# bender_isometer_interface.net
KiCad netlist of a schematic drawn in Altium Designer
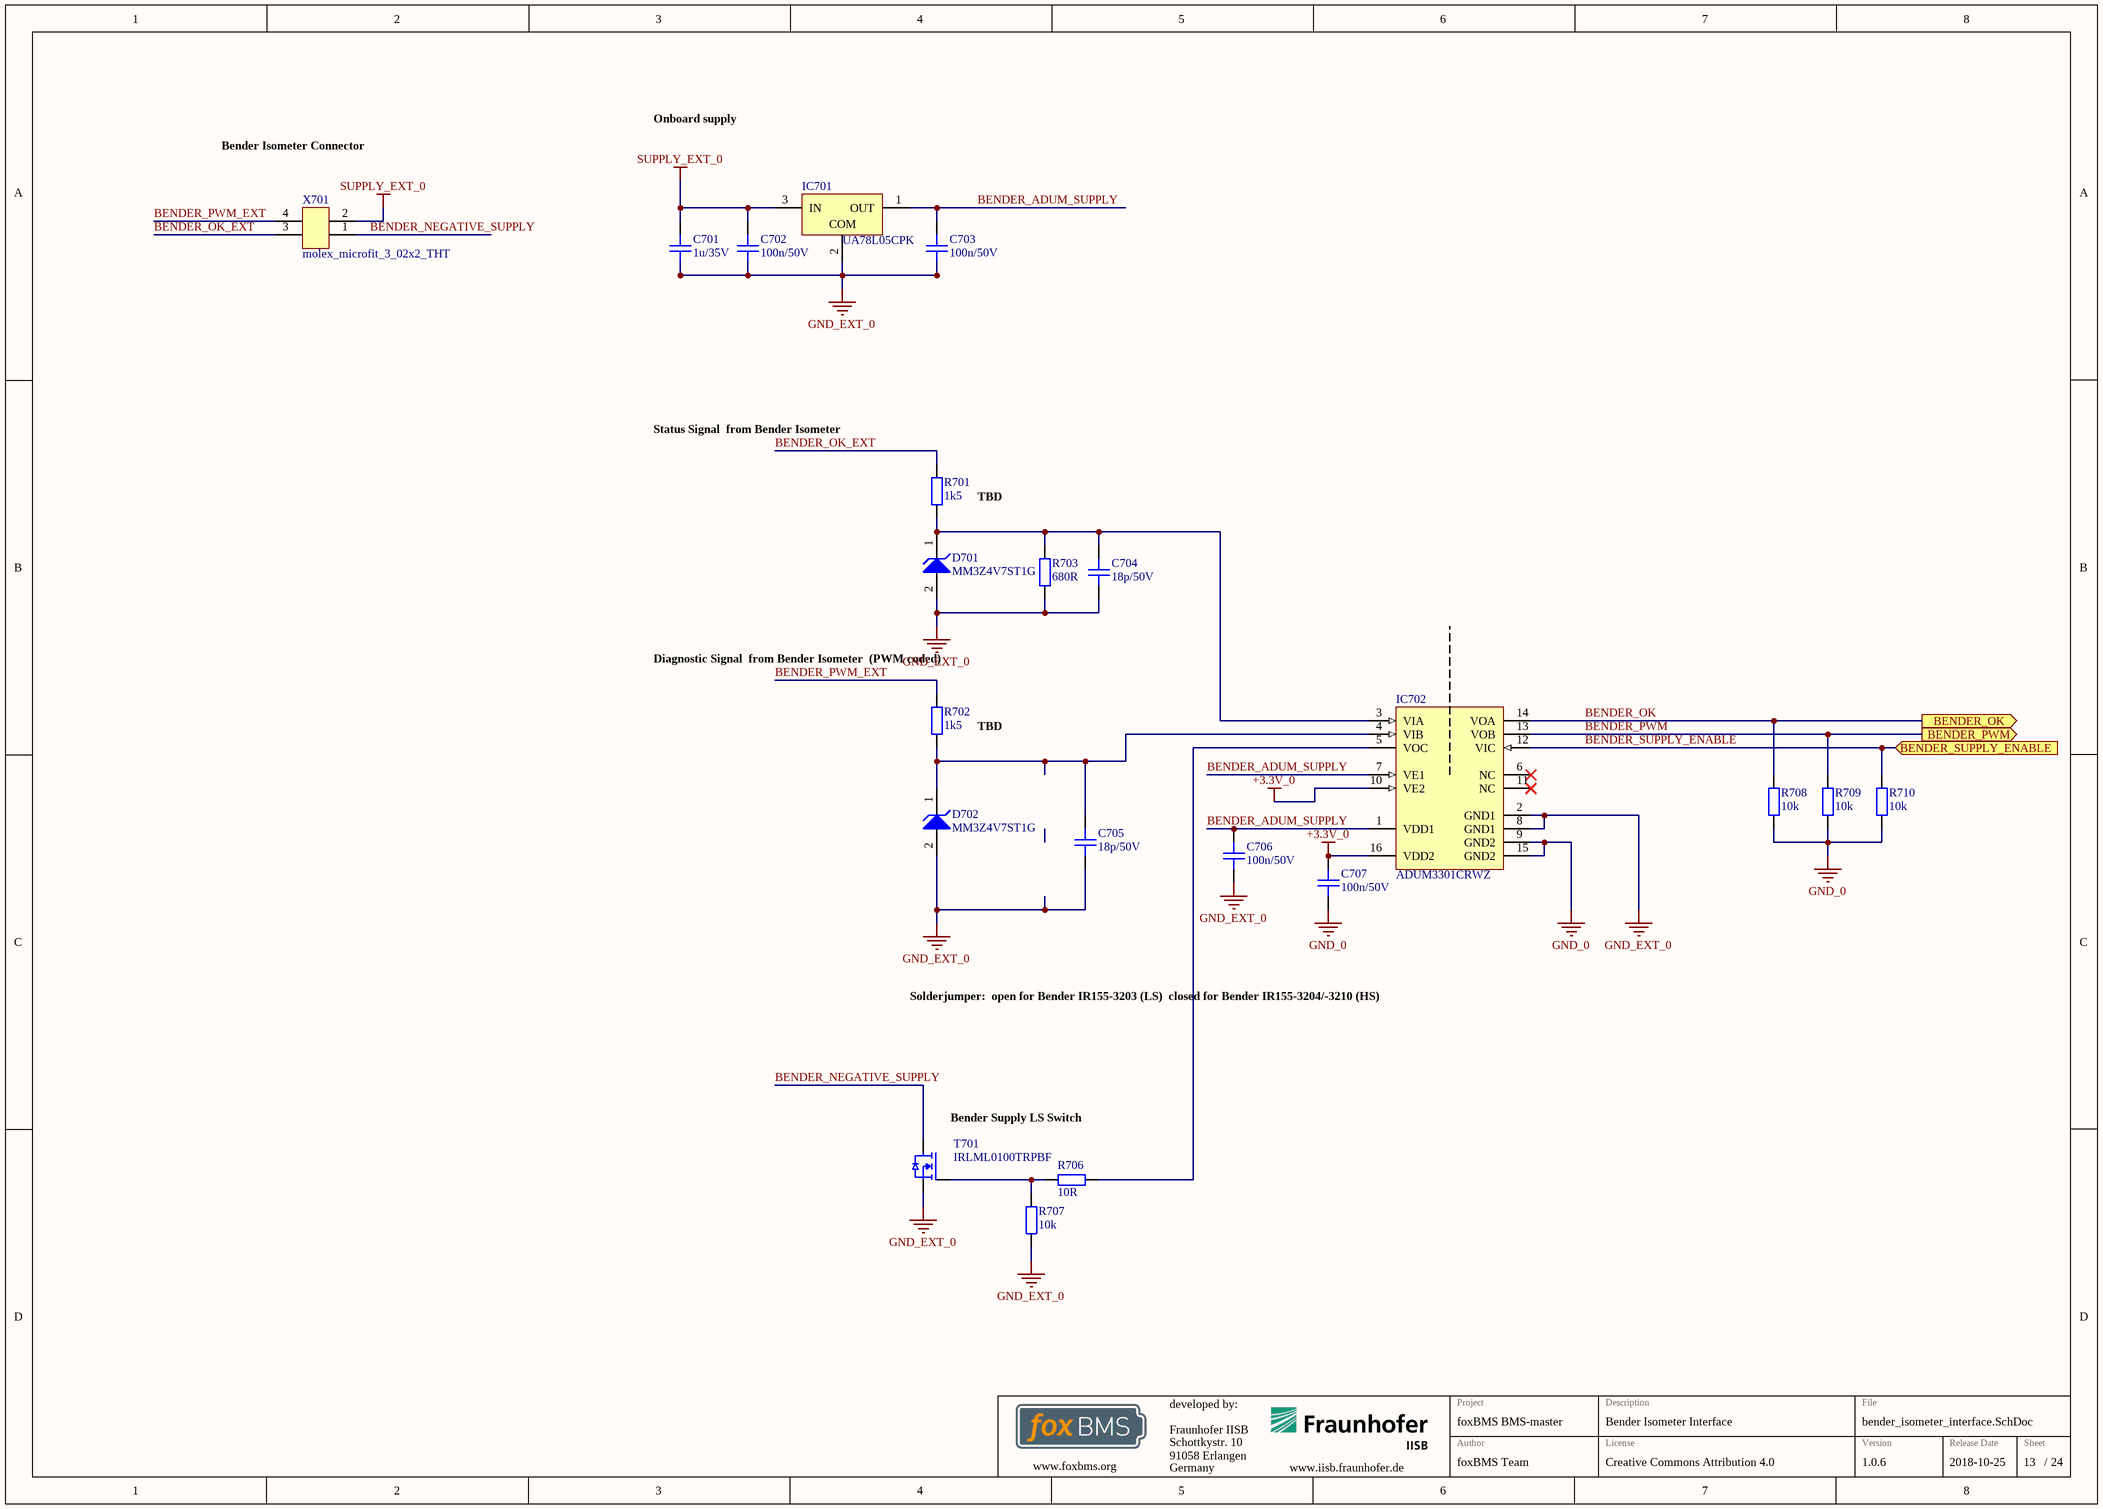
[diagram p0: bender_isometer_interface.SchDoc]

(export (version "E")
  (design (tool "Eeschema 10.0.6"))
  (components
    (comp (ref "C701")
      (value "1u/35V")
      (footprint "CAPC1608X08N")
      (description "MLCC")
      (fields (field (name "PART NUMBER") "gen_C_ceramic_1u_35V_X7R_0603"))
      (libsource (lib "OE750") (part "C"))
    )
    (comp (ref "C702")
      (value "100n/50V")
      (footprint "CAPC1608X08N")
      (description "MLCC")
      (fields (field (name "PART NUMBER") "gen_C_ceramic_100n_50V_X7R_0603"))
      (libsource (lib "OE750") (part "C"))
    )
    (comp (ref "C703")
      (value "100n/50V")
      (footprint "CAPC1608X08N")
      (description "MLCC")
      (fields (field (name "PART NUMBER") "gen_C_ceramic_100n_50V_X7R_0603"))
      (libsource (lib "OE750") (part "C"))
    )
    (comp (ref "C704")
      (value "18p/50V")
      (footprint "CAPC1608X08N")
      (description "MLCC")
      (fields (field (name "PART NUMBER") "gen_C_ceramic_18p_50V_C0G_0603"))
      (libsource (lib "OE750") (part "C"))
    )
    (comp (ref "C705")
      (value "18p/50V")
      (footprint "CAPC1608X08N")
      (description "MLCC")
      (fields (field (name "PART NUMBER") "gen_C_ceramic_18p_50V_C0G_0603"))
      (libsource (lib "OE750") (part "C"))
    )
    (comp (ref "C706")
      (value "100n/50V")
      (footprint "CAPC1608X08N")
      (description "MLCC")
      (fields (field (name "PART NUMBER") "gen_C_ceramic_100n_50V_X7R_0603"))
      (libsource (lib "OE750") (part "C"))
    )
    (comp (ref "C707")
      (value "100n/50V")
      (footprint "CAPC1608X08N")
      (description "MLCC")
      (fields (field (name "PART NUMBER") "gen_C_ceramic_100n_50V_X7R_0603"))
      (libsource (lib "OE750") (part "C"))
    )
    (comp (ref "D701")
      (value "MM3Z4V7ST1G")
      (footprint "ONSC-SOD-323-2-477-02_V")
      (description "Zener Voltage Regulator, 300 mW, Tight Tolerance Portfolio, 2-Pin SOD-323, Pb-Free, Tape and Reel")
      (fields (field (name "MANUFACTURER") "On Semiconductor"))
      (libsource (lib "Altium Content Vault") (part "ONSC-K1A2-2"))
    )
    (comp (ref "D702")
      (value "MM3Z4V7ST1G")
      (footprint "ONSC-SOD-323-2-477-02_V")
      (description "Zener Voltage Regulator, 300 mW, Tight Tolerance Portfolio, 2-Pin SOD-323, Pb-Free, Tape and Reel")
      (fields (field (name "MANUFACTURER") "On Semiconductor"))
      (libsource (lib "Altium Content Vault") (part "ONSC-K1A2-2"))
    )
    (comp (ref "IC701")
      (value "UA78L05CPK")
      (footprint "PK0003A_L")
      (fields (field (name "MANUFACTURER") "TexasInstruments"))
      (libsource (lib "Altium Content Vault") (part "TI-UA78L05-PK-3"))
    )
    (comp (ref "IC702")
      (value "ADUM3301CRWZ")
      (footprint "ADI-RW-16_N")
      (fields (field (name "MANUFACTURER") "Analog Devices"))
      (libsource (lib "Altium Content Vault") (part "ADI-ADUMX301-RW-16"))
    )
    (comp (ref "R701")
      (value "1k5")
      (footprint "RESC1608X05N")
      (description "SMD Resistor 1k5 0603")
      (fields (field (name "PART NUMBER") "gen_R_1k5_0603") (field (name "TOLERANCE") "1%"))
      (libsource (lib "OE750") (part "R"))
    )
    (comp (ref "R702")
      (value "1k5")
      (footprint "RESC1608X05N")
      (description "SMD Resistor 1k5 0603")
      (fields (field (name "PART NUMBER") "gen_R_1k5_0603") (field (name "TOLERANCE") "1%"))
      (libsource (lib "OE750") (part "R"))
    )
    (comp (ref "R703")
      (value "680R")
      (footprint "RESC1608X05N")
      (description "SMD Resistor 680R 0603")
      (fields (field (name "PART NUMBER") "gen_R_680R_0603") (field (name "TOLERANCE") "1%"))
      (libsource (lib "OE750") (part "R"))
    )
    (comp (ref "R706")
      (value "10R")
      (footprint "RESC1608X05N")
      (description "SMD Resistor 10R 0603")
      (fields (field (name "PART NUMBER") "gen_R_10R_0603") (field (name "TOLERANCE") "1%"))
      (libsource (lib "OE750") (part "R"))
    )
    (comp (ref "R707")
      (value "10k")
      (footprint "RESC1608X05N")
      (description "SMD Resistor 10k 0603")
      (fields (field (name "PART NUMBER") "gen_R_10k_0603") (field (name "TOLERANCE") "1%"))
      (libsource (lib "OE750") (part "R"))
    )
    (comp (ref "R708")
      (value "10k")
      (footprint "RESC1608X05N")
      (description "SMD Resistor 10k 0603")
      (fields (field (name "PART NUMBER") "gen_R_10k_0603") (field (name "TOLERANCE") "1%"))
      (libsource (lib "OE750") (part "R"))
    )
    (comp (ref "R709")
      (value "10k")
      (footprint "RESC1608X05N")
      (description "SMD Resistor 10k 0603")
      (fields (field (name "PART NUMBER") "gen_R_10k_0603") (field (name "TOLERANCE") "1%"))
      (libsource (lib "OE750") (part "R"))
    )
    (comp (ref "R710")
      (value "10k")
      (footprint "RESC1608X05N")
      (description "SMD Resistor 10k 0603")
      (fields (field (name "PART NUMBER") "gen_R_10k_0603") (field (name "TOLERANCE") "1%"))
      (libsource (lib "OE750") (part "R"))
    )
    (comp (ref "T701")
      (value "IRLML0100TRPBF")
      (footprint "SOT95P237X110-3N")
      (description "MOSFET-Transistor, n-Kanal, 1.6 A, 100 V, 0.178 ohm, 10 V, 2.5 V")
      (fields (field (name "MANUFACTURER") "Infineon"))
      (libsource (lib "OE750") (part "NMOS"))
    )
    (comp (ref "X701")
      (value "molex_microfit_3_02x2_THT")
      (footprint "MOLEX_MICROFIT_02x2_THT")
      (fields (field (name "MANUFACTURER") "Molex"))
      (libsource (lib "OE750") (part "X2x2"))
    )
  )
  (nets
    (net (code "1") (name "+3.3V_0") (class "Default")
      (node (ref "C707") (pin "1") (pinfunction "1_1") (pintype "passive"))
      (node (ref "IC702") (pin "10") (pinfunction "VE2_10") (pintype "input"))
      (node (ref "IC702") (pin "16") (pinfunction "VDD2_16") (pintype "power_in"))
    )
    (net (code "2") (name "/BENDER_ADUM_SUPPLY") (class "Default")
      (node (ref "C703") (pin "1") (pinfunction "1_1") (pintype "passive"))
      (node (ref "C706") (pin "1") (pinfunction "1_1") (pintype "passive"))
      (node (ref "IC701") (pin "1") (pinfunction "OUT_1") (pintype "power_in"))
      (node (ref "IC702") (pin "1") (pinfunction "VDD1_1") (pintype "power_in"))
      (node (ref "IC702") (pin "7") (pinfunction "VE1_7") (pintype "input"))
    )
    (net (code "3") (name "/BENDER_NEGATIVE_SUPPLY") (class "Default")
      (node (ref "T701") (pin "D") (pinfunction "D_D") (pintype "passive"))
      (node (ref "X701") (pin "1") (pintype "passive"))
    )
    (net (code "4") (name "/BENDER_OK") (class "Default")
      (node (ref "IC702") (pin "14") (pinfunction "VOA_14") (pintype "tri_state"))
      (node (ref "R708") (pin "2") (pinfunction "2_2") (pintype "passive"))
    )
    (net (code "5") (name "/BENDER_OK_EXT") (class "Default")
      (node (ref "R701") (pin "2") (pinfunction "2_2") (pintype "passive"))
      (node (ref "X701") (pin "3") (pintype "passive"))
    )
    (net (code "6") (name "/BENDER_PWM") (class "Default")
      (node (ref "IC702") (pin "13") (pinfunction "VOB_13") (pintype "tri_state"))
      (node (ref "R709") (pin "2") (pinfunction "2_2") (pintype "passive"))
    )
    (net (code "7") (name "/BENDER_PWM_EXT") (class "Default")
      (node (ref "R702") (pin "2") (pinfunction "2_2") (pintype "passive"))
      (node (ref "X701") (pin "4") (pintype "passive"))
    )
    (net (code "8") (name "/BENDER_SUPPLY_ENABLE") (class "Default")
      (node (ref "IC702") (pin "12") (pinfunction "VIC_12") (pintype "input"))
      (node (ref "R710") (pin "2") (pinfunction "2_2") (pintype "passive"))
    )
    (net (code "9") (name "GND_0") (class "Default")
      (node (ref "C707") (pin "2") (pinfunction "2_2") (pintype "passive"))
      (node (ref "IC702") (pin "15") (pinfunction "GND2_15") (pintype "power_in"))
      (node (ref "IC702") (pin "9") (pinfunction "GND2_9") (pintype "power_in"))
      (node (ref "R708") (pin "1") (pinfunction "1_1") (pintype "passive"))
      (node (ref "R709") (pin "1") (pinfunction "1_1") (pintype "passive"))
      (node (ref "R710") (pin "1") (pinfunction "1_1") (pintype "passive"))
    )
    (net (code "10") (name "GND_EXT_0") (class "Default")
      (node (ref "C701") (pin "2") (pinfunction "2_2") (pintype "passive"))
      (node (ref "C702") (pin "2") (pinfunction "2_2") (pintype "passive"))
      (node (ref "C703") (pin "2") (pinfunction "2_2") (pintype "passive"))
      (node (ref "C704") (pin "2") (pinfunction "2_2") (pintype "passive"))
      (node (ref "C705") (pin "2") (pinfunction "2_2") (pintype "passive"))
      (node (ref "C706") (pin "2") (pinfunction "2_2") (pintype "passive"))
      (node (ref "D701") (pin "2") (pinfunction "A_2") (pintype "passive"))
      (node (ref "D702") (pin "2") (pinfunction "A_2") (pintype "passive"))
      (node (ref "IC701") (pin "2") (pinfunction "COM_2") (pintype "power_in"))
      (node (ref "IC702") (pin "2") (pinfunction "GND1_2") (pintype "power_in"))
      (node (ref "IC702") (pin "8") (pinfunction "GND1_8") (pintype "power_in"))
      (node (ref "R703") (pin "1") (pinfunction "1_1") (pintype "passive"))
      (node (ref "R707") (pin "2") (pinfunction "2_2") (pintype "passive"))
      (node (ref "T701") (pin "S") (pinfunction "S_S") (pintype "passive"))
    )
    (net (code "11") (name "Net-(D701-K)") (class "Default")
      (node (ref "C704") (pin "1") (pinfunction "1_1") (pintype "passive"))
      (node (ref "D701") (pin "1") (pinfunction "K_1") (pintype "passive"))
      (node (ref "IC702") (pin "3") (pinfunction "VIA_3") (pintype "input"))
      (node (ref "R701") (pin "1") (pinfunction "1_1") (pintype "passive"))
      (node (ref "R703") (pin "2") (pinfunction "2_2") (pintype "passive"))
    )
    (net (code "12") (name "Net-(D702-K)") (class "Default")
      (node (ref "C705") (pin "1") (pinfunction "1_1") (pintype "passive"))
      (node (ref "D702") (pin "1") (pinfunction "K_1") (pintype "passive"))
      (node (ref "IC702") (pin "4") (pinfunction "VIB_4") (pintype "input"))
      (node (ref "R702") (pin "1") (pinfunction "1_1") (pintype "passive"))
    )
    (net (code "13") (name "Net-(IC702-VOC)") (class "Default")
      (node (ref "IC702") (pin "5") (pinfunction "VOC_5") (pintype "tri_state"))
      (node (ref "R706") (pin "1") (pinfunction "1_1") (pintype "passive"))
    )
    (net (code "14") (name "Net-(R706-Pad2)") (class "Default")
      (node (ref "R706") (pin "2") (pinfunction "2_2") (pintype "passive"))
      (node (ref "R707") (pin "1") (pinfunction "1_1") (pintype "passive"))
      (node (ref "T701") (pin "G") (pinfunction "G_G") (pintype "passive"))
    )
    (net (code "15") (name "SUPPLY_EXT_0") (class "Default")
      (node (ref "C701") (pin "1") (pinfunction "1_1") (pintype "passive"))
      (node (ref "C702") (pin "1") (pinfunction "1_1") (pintype "passive"))
      (node (ref "IC701") (pin "3") (pinfunction "IN_3") (pintype "power_in"))
      (node (ref "X701") (pin "2") (pintype "passive"))
    )
    (net (code "16") (name "unconnected-(IC702-NC-Pad6)") (class "Default")
      (node (ref "IC702") (pin "6") (pinfunction "NC_6") (pintype "passive+no_connect"))
    )
    (net (code "17") (name "unconnected-(IC702-NC-Pad11)") (class "Default")
      (node (ref "IC702") (pin "11") (pinfunction "NC_11") (pintype "passive+no_connect"))
    )
  )
)
